# Power.net
KiCad netlist of a schematic drawn in Altium Designer
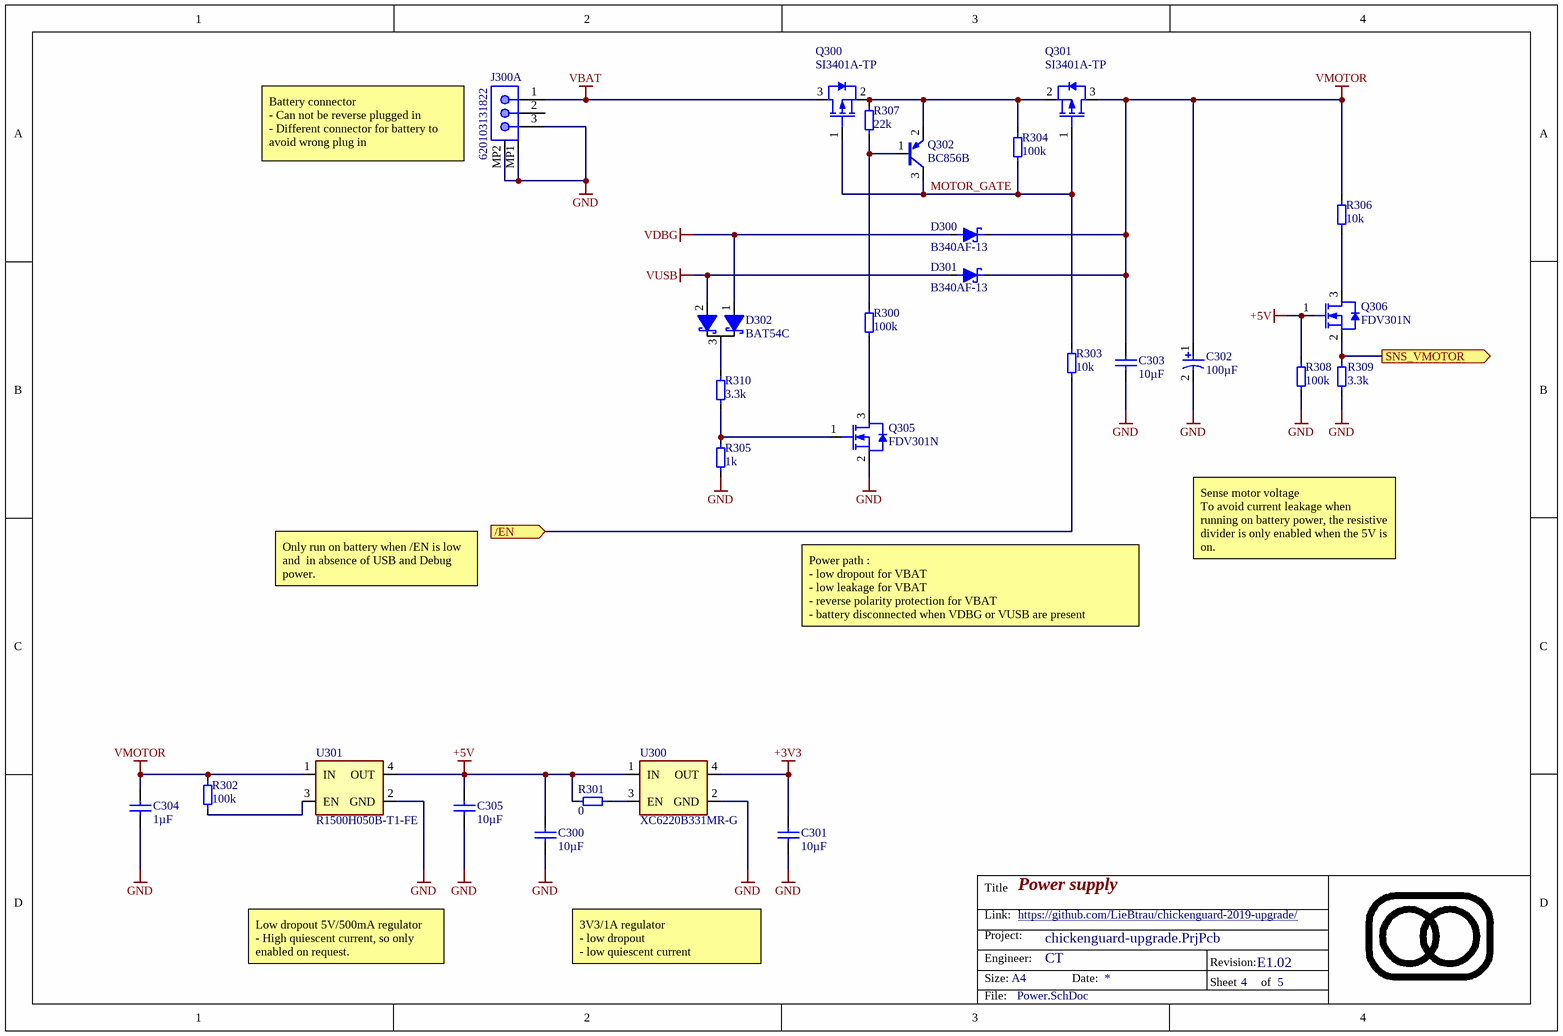
[diagram p0: Power.SchDoc]

(export (version "E")
  (design (tool "Eeschema 10.0.6"))
  (components
    (comp (ref "C300")
      (value "10µF")
      (footprint "0805-C-L")
      (description "WCAP-CSGP Multilayer Ceramic Chip Capacitor, General Purpose, size 0805, X7R, 10µF, 10VDC")
      (fields (field (name "TOLERANCE") "10%") (field (name "JLCPCB PART #") "C15850"))
      (libsource (lib "7c7 Engineering") (part "CAP-NP-2"))
    )
    (comp (ref "C301")
      (value "10µF")
      (footprint "0805-C-L")
      (description "WCAP-CSGP Multilayer Ceramic Chip Capacitor, General Purpose, size 0805, X7R, 10µF, 10VDC")
      (fields (field (name "TOLERANCE") "10%") (field (name "JLCPCB PART #") "C15850"))
      (libsource (lib "7c7 Engineering") (part "CAP-NP-2"))
    )
    (comp (ref "C302")
      (value "100µF")
      (footprint "WCAP-ASLL_D6.3H5.5")
      (description "WCAP-ASLL Aluminum Electrolytic Capacitor, V-Chip, SMT, D6.3xH5.5mm, 100uF, 10V")
      (fields (field (name "TOLERANCE") "20%") (field (name "Comment") "865060243004"))
      (libsource (lib "7c7 Engineering") (part "CAP-P-2"))
    )
    (comp (ref "C303")
      (value "10µF")
      (footprint "0805-C-L")
      (description "WCAP-CSGP Multilayer Ceramic Chip Capacitor, General Purpose, size 0805, X7R, 10µF, 10VDC")
      (fields (field (name "TOLERANCE") "10%") (field (name "JLCPCB PART #") "C15850"))
      (libsource (lib "7c7 Engineering") (part "CAP-NP-2"))
    )
    (comp (ref "C304")
      (value "1µF")
      (footprint "0603-C-N")
      (description "Capacitor MLCC, General Purpose, size 0603, X7R, 1µF, +/-10%, 16V")
      (fields (field (name "TOLERANCE") "10%") (field (name "JLCPCB PART #") "C15849"))
      (libsource (lib "7c7 Engineering") (part "CAP-NP-2"))
    )
    (comp (ref "C305")
      (value "10µF")
      (footprint "0805-C-L")
      (description "WCAP-CSGP Multilayer Ceramic Chip Capacitor, General Purpose, size 0805, X7R, 10µF, 10VDC")
      (fields (field (name "TOLERANCE") "10%") (field (name "JLCPCB PART #") "C15850"))
      (libsource (lib "7c7 Engineering") (part "CAP-NP-2"))
    )
    (comp (ref "D300")
      (value "B340AF-13")
      (footprint "DO-214AC_UNI")
      (description "Diode 40 V 3A Surface Mount SMAF")
      (libsource (lib "7c7 Engineering") (part "DIODE-SKY-2"))
    )
    (comp (ref "D301")
      (value "B340AF-13")
      (footprint "DO-214AC_UNI")
      (description "Diode 40 V 3A Surface Mount SMAF")
      (libsource (lib "7c7 Engineering") (part "DIODE-SKY-2"))
    )
    (comp (ref "D302")
      (value "BAT54C")
      (footprint "SOT-23-3-N")
      (description "Rectifier Diode Small Signal Schottky 30V 0.2A 5ns Automotive 3-Pin SOT-23 T/R")
      (fields (field (name "VOLTAGE") "30V"))
      (libsource (lib "7c7 Engineering") (part "D_SKY_COMMON_CATHODE"))
    )
    (comp (ref "J300")
      (value "620103131822")
      (footprint "620103131822")
      (description "WR-WTB SMT Male Horizontal Shrouded Header, pitch 2mm, 3p")
      (fields (field (name "PUBLISHER") "Wurth Elektronik"))
      (libsource (lib "7c7 Engineering") (part "HDR_3P"))
    )
    (comp (ref "Q300")
      (value "SI3401A-TP")
      (footprint "SOT-23-3-N")
      (description "Trans Mosfet P-ch 30V 4.2A 3-PIN SOT-23 T/r")
      (fields (field (name "JLCPCB PART #") "C194253"))
      (libsource (lib "7c7 Engineering") (part "PEMOS-GSD-3"))
    )
    (comp (ref "Q301")
      (value "SI3401A-TP")
      (footprint "SOT-23-3-N")
      (description "Trans Mosfet P-ch 30V 4.2A 3-PIN SOT-23 T/r")
      (fields (field (name "JLCPCB PART #") "C194253"))
      (libsource (lib "7c7 Engineering") (part "PEMOS-GSD-3"))
    )
    (comp (ref "Q302")
      (value "BC856B")
      (footprint "SOT-23-3-N")
      (description "Bipolar Transistor, SOT-23, 65V, 100mA, PNP")
      (fields (field (name "VOLTAGE") "65V"))
      (libsource (lib "7c7 Engineering") (part "BJT-PNP-BEC"))
    )
    (comp (ref "Q305")
      (value "FDV301N")
      (footprint "SOT-23-3-N")
      (description "Transistor MOSFET N-Ch. 25V 220mA 0, 35W 4Ohm SOT23")
      (fields (field (name "JLCPCB PART #") "C15310"))
      (libsource (lib "7c7 Engineering") (part "NEMOS-GSD-3"))
    )
    (comp (ref "Q306")
      (value "FDV301N")
      (footprint "SOT-23-3-N")
      (description "Transistor MOSFET N-Ch. 25V 220mA 0, 35W 4Ohm SOT23")
      (fields (field (name "JLCPCB PART #") "C15310"))
      (libsource (lib "7c7 Engineering") (part "NEMOS-GSD-3"))
    )
    (comp (ref "R300")
      (value "100k")
      (footprint "0603-R-N")
      (description "Chip Resistor, Thick Film, General Purpose, 0603, 100mW, 50V, 100 kOhm, +/-1%")
      (fields (field (name "JLCPCB PART #") "C25803") (field (name "TOLERANCE") "1%"))
      (libsource (lib "7c7 Engineering") (part "RES"))
    )
    (comp (ref "R301")
      (value "0")
      (footprint "0603-R-N")
      (description "Chip Jumper, Thick Film, Jumper, 0603, 100mW, 1A, 0 Ohm, <50 mOhm")
      (fields (field (name "TOLERANCE") "50 mOhm") (field (name "JLCPCB PART #") "C21189"))
      (libsource (lib "") (part "RES_2"))
    )
    (comp (ref "R302")
      (value "100k")
      (footprint "0603-R-N")
      (description "Chip Resistor, Thick Film, General Purpose, 0603, 100mW, 50V, 100 kOhm, +/-1%")
      (fields (field (name "JLCPCB PART #") "C25803") (field (name "TOLERANCE") "1%"))
      (libsource (lib "") (part "RES_1"))
    )
    (comp (ref "R303")
      (value "10k")
      (footprint "0603-R-N")
      (description "Chip Resistor, Thick Film, General Purpose, 0603, 100mW, 50V, 10 kOhm, +/-1%")
      (fields (field (name "JLCPCB PART #") "C25804") (field (name "TOLERANCE") "1%"))
      (libsource (lib "7c7 Engineering") (part "RES"))
    )
    (comp (ref "R304")
      (value "100k")
      (footprint "0603-R-N")
      (description "Chip Resistor, Thick Film, General Purpose, 0603, 100mW, 50V, 100 kOhm, +/-1%")
      (fields (field (name "JLCPCB PART #") "C25803") (field (name "TOLERANCE") "1%"))
      (libsource (lib "7c7 Engineering") (part "RES"))
    )
    (comp (ref "R305")
      (value "1k")
      (footprint "0603-R-N")
      (description "Chip Resistor, Thick Film, General Purpose, 0603, 100mW, 50V, 1 kOhm, +/-1%")
      (fields (field (name "JLCPCB PART #") "C116692") (field (name "TOLERANCE") "1%"))
      (libsource (lib "7c7 Engineering") (part "RES"))
    )
    (comp (ref "R306")
      (value "10k")
      (footprint "0603-R-N")
      (description "Chip Resistor, Thick Film, General Purpose, 0603, 100mW, 50V, 10 kOhm, +/-1%")
      (fields (field (name "JLCPCB PART #") "C25804") (field (name "TOLERANCE") "1%"))
      (libsource (lib "7c7 Engineering") (part "RES"))
    )
    (comp (ref "R307")
      (value "22k")
      (footprint "0603-R-N")
      (description "Chip Resistor, Thick Film, General Purpose, 0603, 100mW, 50V, 22 kOhm, +/-1%")
      (fields (field (name "TOLERANCE") "1%") (field (name "Comment") "Resistor 22k +/-1% 50V 0603"))
      (libsource (lib "7c7 Engineering") (part "RES"))
    )
    (comp (ref "R308")
      (value "100k")
      (footprint "0603-R-N")
      (description "Chip Resistor, Thick Film, General Purpose, 0603, 100mW, 50V, 100 kOhm, +/-1%")
      (fields (field (name "JLCPCB PART #") "C25803") (field (name "TOLERANCE") "1%"))
      (libsource (lib "") (part "RES_1"))
    )
    (comp (ref "R309")
      (value "3.3k")
      (footprint "0603-R-N")
      (description "Chip Resistor, Thick Film, General Purpose, 0603, 100mW, 50V, 3.3 kOhm, +/-1%")
      (fields (field (name "TOLERANCE") "1%") (field (name "JLCPCB PART #") "C22978"))
      (libsource (lib "") (part "RES_1"))
    )
    (comp (ref "R310")
      (value "3.3k")
      (footprint "0603-R-N")
      (description "Chip Resistor, Thick Film, General Purpose, 0603, 100mW, 50V, 3.3 kOhm, +/-1%")
      (fields (field (name "JLCPCB PART #") "C22978") (field (name "TOLERANCE") "1%"))
      (libsource (lib "7c7 Engineering") (part "RES"))
    )
    (comp (ref "U300")
      (value "XC6220B331MR-G")
      (footprint "SOT25-N")
      (description "Linear Voltage Regulator IC Positive Fixed 1 Output 1A SOT-25-5")
      (libsource (lib "7c7 Engineering") (part "LDO-with-enable"))
    )
    (comp (ref "U301")
      (value "R1500H050B-T1-FE")
      (footprint "SOT-89-MT5_N")
      (description "LDO Regulator Pos 5V 0.5A Automotive 6-Pin(5+Tab) SOT-89 T/R")
      (libsource (lib "7c7 Engineering") (part "LDO-with-enable"))
    )
  )
  (nets
    (net (code "1") (name "+3V3") (class "Default")
      (node (ref "C301") (pin "1") (pinfunction "1_1") (pintype "passive"))
      (node (ref "U300") (pin "4") (pinfunction "OUT_4") (pintype "power_in"))
    )
    (net (code "2") (name "+5V") (class "Default")
      (node (ref "C300") (pin "1") (pinfunction "1_1") (pintype "passive"))
      (node (ref "C305") (pin "1") (pinfunction "1_1") (pintype "passive"))
      (node (ref "Q306") (pin "1") (pinfunction "G_1") (pintype "passive"))
      (node (ref "R301") (pin "1") (pinfunction "1_1") (pintype "passive"))
      (node (ref "R308") (pin "1") (pinfunction "1_1") (pintype "passive"))
      (node (ref "U300") (pin "1") (pinfunction "IN_1") (pintype "power_in"))
      (node (ref "U301") (pin "4") (pinfunction "OUT_4") (pintype "power_in"))
    )
    (net (code "3") (name "/MOTOR_GATE") (class "Default")
      (node (ref "Q300") (pin "1") (pinfunction "GATE_1") (pintype "passive"))
      (node (ref "Q301") (pin "1") (pinfunction "GATE_1") (pintype "passive"))
      (node (ref "Q302") (pin "3") (pinfunction "C_3") (pintype "passive"))
      (node (ref "R303") (pin "2") (pinfunction "2_2") (pintype "passive"))
      (node (ref "R304") (pin "1") (pinfunction "1_1") (pintype "passive"))
    )
    (net (code "4") (name "/SNS_VMOTOR") (class "Default")
      (node (ref "Q306") (pin "2") (pinfunction "S_2") (pintype "passive"))
      (node (ref "R309") (pin "1") (pinfunction "1_1") (pintype "passive"))
    )
    (net (code "5") (name "/{slash}EN") (class "Default")
      (node (ref "R303") (pin "1") (pinfunction "1_1") (pintype "passive"))
    )
    (net (code "6") (name "GND") (class "Default")
      (node (ref "C300") (pin "2") (pinfunction "2_2") (pintype "passive"))
      (node (ref "C301") (pin "2") (pinfunction "2_2") (pintype "passive"))
      (node (ref "C302") (pin "2") (pinfunction "2_2") (pintype "passive"))
      (node (ref "C303") (pin "2") (pinfunction "2_2") (pintype "passive"))
      (node (ref "C304") (pin "2") (pinfunction "2_2") (pintype "passive"))
      (node (ref "C305") (pin "2") (pinfunction "2_2") (pintype "passive"))
      (node (ref "J300") (pin "3") (pinfunction "3_3") (pintype "passive"))
      (node (ref "J300") (pin "MP1") (pinfunction "MP1_MP1") (pintype "passive"))
      (node (ref "J300") (pin "MP2") (pinfunction "MP2_MP2") (pintype "passive"))
      (node (ref "Q305") (pin "2") (pinfunction "S_2") (pintype "passive"))
      (node (ref "R305") (pin "1") (pinfunction "1_1") (pintype "passive"))
      (node (ref "R308") (pin "2") (pinfunction "2_2") (pintype "passive"))
      (node (ref "R309") (pin "2") (pinfunction "2_2") (pintype "passive"))
      (node (ref "U300") (pin "2") (pinfunction "GND_2") (pintype "power_in"))
      (node (ref "U301") (pin "2") (pinfunction "GND_2") (pintype "power_in"))
    )
    (net (code "7") (name "Net-(D302-A)") (class "Default")
      (node (ref "D302") (pin "3") (pinfunction "A_3") (pintype "passive"))
      (node (ref "R310") (pin "2") (pinfunction "2_2") (pintype "passive"))
    )
    (net (code "8") (name "Net-(Q300-SOURCE)") (class "Default")
      (node (ref "Q300") (pin "2") (pinfunction "SOURCE_2") (pintype "passive"))
      (node (ref "Q301") (pin "2") (pinfunction "SOURCE_2") (pintype "passive"))
      (node (ref "Q302") (pin "2") (pinfunction "E_2") (pintype "passive"))
      (node (ref "R304") (pin "2") (pinfunction "2_2") (pintype "passive"))
      (node (ref "R307") (pin "2") (pinfunction "2_2") (pintype "passive"))
    )
    (net (code "9") (name "Net-(Q302-B)") (class "Default")
      (node (ref "Q302") (pin "1") (pinfunction "B_1") (pintype "passive"))
      (node (ref "R300") (pin "2") (pinfunction "2_2") (pintype "passive"))
      (node (ref "R307") (pin "1") (pinfunction "1_1") (pintype "passive"))
    )
    (net (code "10") (name "Net-(Q305-D)") (class "Default")
      (node (ref "Q305") (pin "3") (pinfunction "D_3") (pintype "passive"))
      (node (ref "R300") (pin "1") (pinfunction "1_1") (pintype "passive"))
    )
    (net (code "11") (name "Net-(Q305-G)") (class "Default")
      (node (ref "Q305") (pin "1") (pinfunction "G_1") (pintype "passive"))
      (node (ref "R305") (pin "2") (pinfunction "2_2") (pintype "passive"))
      (node (ref "R310") (pin "1") (pinfunction "1_1") (pintype "passive"))
    )
    (net (code "12") (name "Net-(Q306-D)") (class "Default")
      (node (ref "Q306") (pin "3") (pinfunction "D_3") (pintype "passive"))
      (node (ref "R306") (pin "1") (pinfunction "1_1") (pintype "passive"))
    )
    (net (code "13") (name "Net-(U300-EN)") (class "Default")
      (node (ref "R301") (pin "2") (pinfunction "2_2") (pintype "passive"))
      (node (ref "U300") (pin "3") (pinfunction "EN_3") (pintype "passive"))
    )
    (net (code "14") (name "Net-(U301-EN)") (class "Default")
      (node (ref "R302") (pin "2") (pinfunction "2_2") (pintype "passive"))
      (node (ref "U301") (pin "3") (pinfunction "EN_3") (pintype "passive"))
    )
    (net (code "15") (name "VBAT") (class "Default")
      (node (ref "J300") (pin "1") (pinfunction "1_1") (pintype "passive"))
      (node (ref "Q300") (pin "3") (pinfunction "DRAIN_3") (pintype "passive"))
    )
    (net (code "16") (name "VDBG") (class "Default")
      (node (ref "D300") (pin "2") (pinfunction "A_2") (pintype "passive"))
      (node (ref "D302") (pin "1") (pinfunction "C1_1") (pintype "passive"))
    )
    (net (code "17") (name "VMOTOR") (class "Default")
      (node (ref "C302") (pin "1") (pinfunction "1_1") (pintype "passive"))
      (node (ref "C303") (pin "1") (pinfunction "1_1") (pintype "passive"))
      (node (ref "C304") (pin "1") (pinfunction "1_1") (pintype "passive"))
      (node (ref "D300") (pin "1") (pinfunction "K_1") (pintype "passive"))
      (node (ref "D301") (pin "1") (pinfunction "K_1") (pintype "passive"))
      (node (ref "Q301") (pin "3") (pinfunction "DRAIN_3") (pintype "passive"))
      (node (ref "R302") (pin "1") (pinfunction "1_1") (pintype "passive"))
      (node (ref "R306") (pin "2") (pinfunction "2_2") (pintype "passive"))
      (node (ref "U301") (pin "1") (pinfunction "IN_1") (pintype "power_in"))
    )
    (net (code "18") (name "VUSB") (class "Default")
      (node (ref "D301") (pin "2") (pinfunction "A_2") (pintype "passive"))
      (node (ref "D302") (pin "2") (pinfunction "C2_2") (pintype "passive"))
    )
    (net (code "19") (name "unconnected-(J300-Pad2)") (class "Default")
      (node (ref "J300") (pin "2") (pinfunction "2_2") (pintype "passive"))
    )
  )
)
